# 9volt_rail.net
KiCad netlist of a schematic drawn in EAGLE
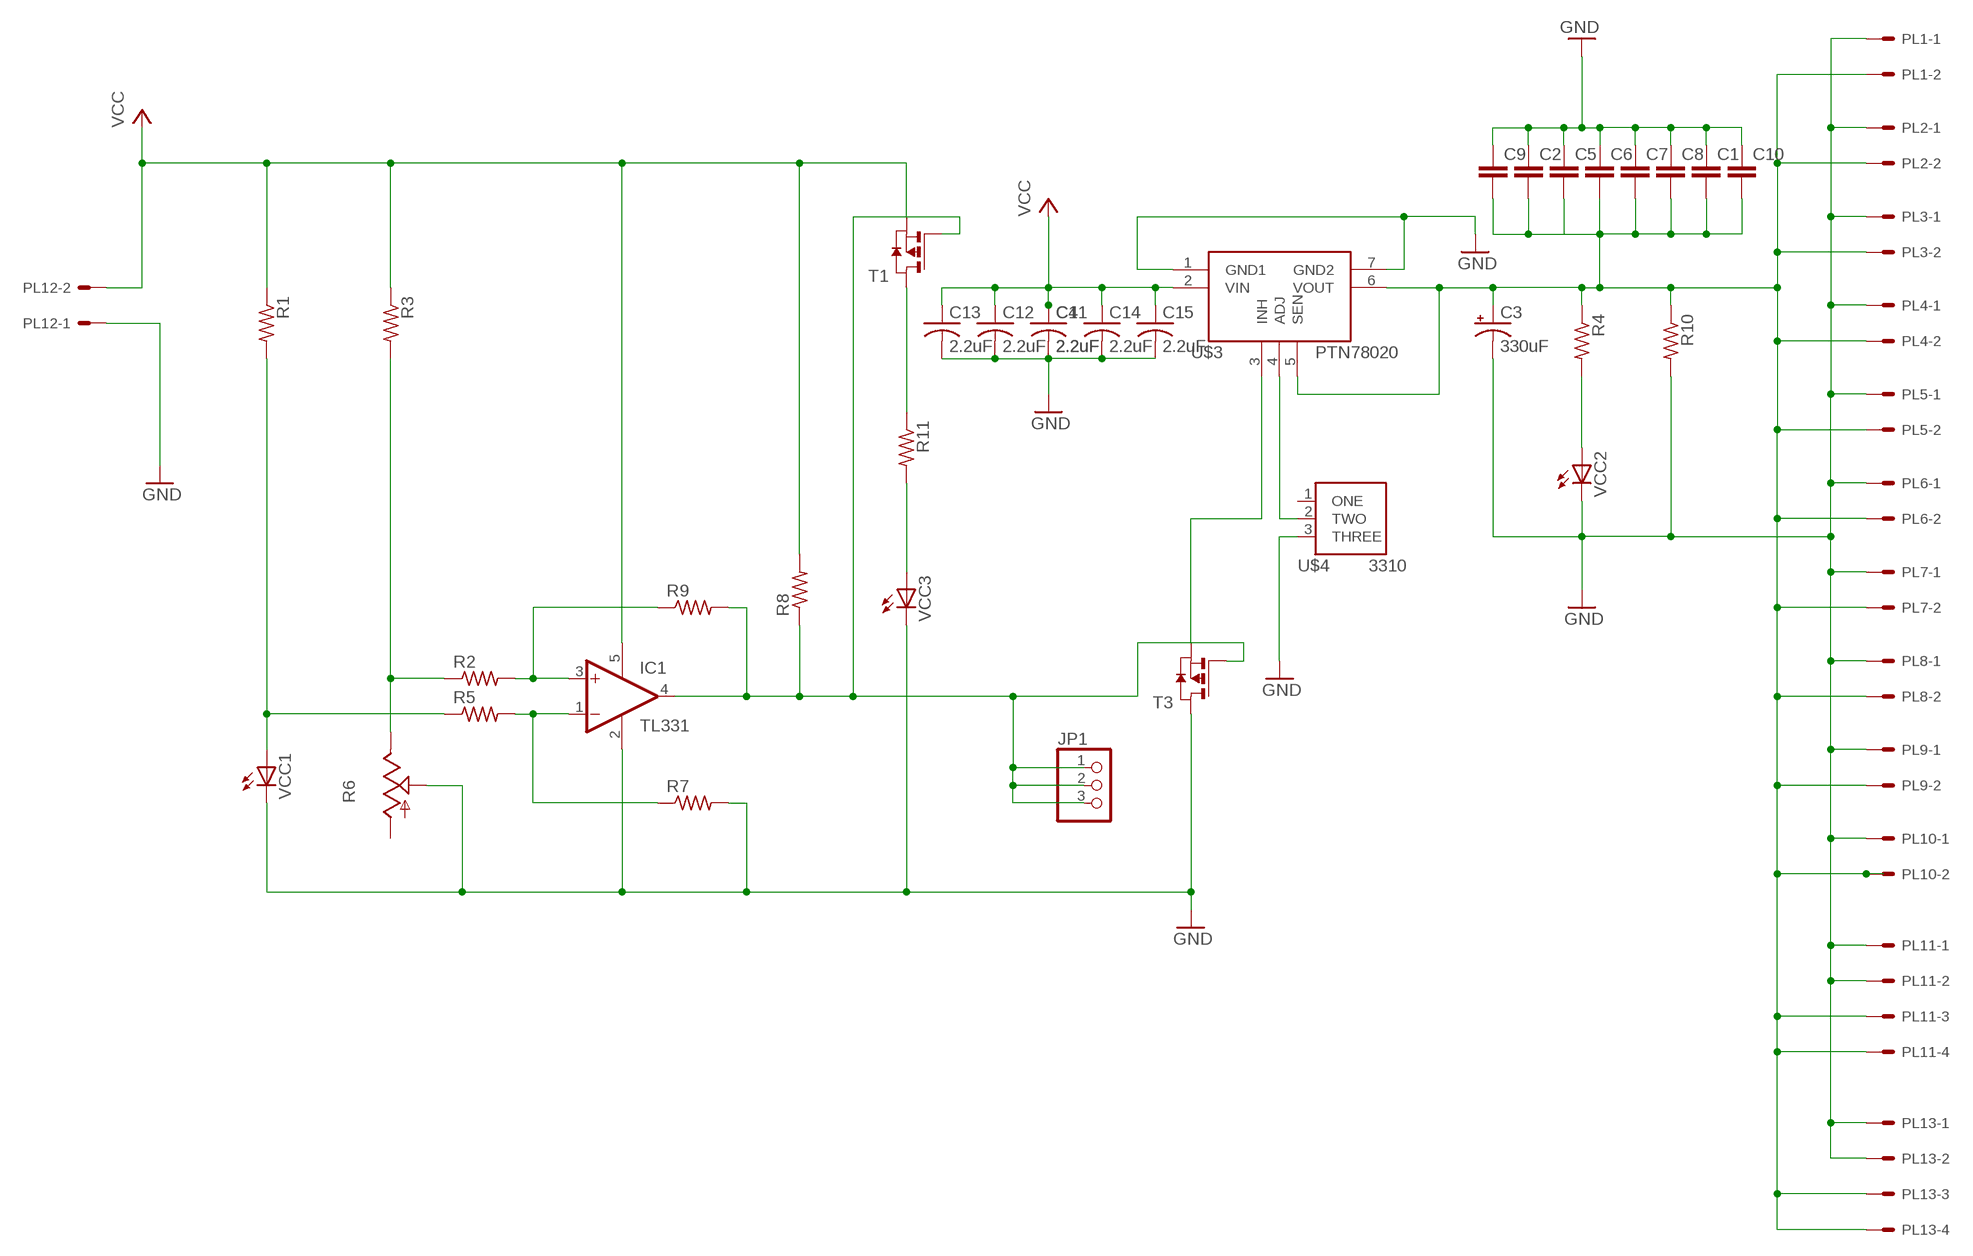
[diagram p0: schematic, sheet 1]

(export (version "E")
  (design (tool "Eeschema 10.0.6"))
  (components
    (comp (ref "C1")
      (value "C-EUC0805")
      (footprint "eagle-import:C0805")
      (libsource (lib "eagle-import") (part "C-EUC0805"))
    )
    (comp (ref "C2")
      (value "C-EUC0805")
      (footprint "eagle-import:C0805")
      (libsource (lib "eagle-import") (part "C-EUC0805"))
    )
    (comp (ref "C3")
      (value "330uF")
      (footprint "eagle-import:E5-10,5")
      (libsource (lib "eagle-import") (part "CPOL-USE5-10.5"))
    )
    (comp (ref "C4")
      (value "2.2uF")
      (footprint "eagle-import:C0805")
      (libsource (lib "eagle-import") (part "C-USC0805"))
    )
    (comp (ref "C5")
      (value "C-EUC0805")
      (footprint "eagle-import:C0805")
      (libsource (lib "eagle-import") (part "C-EUC0805"))
    )
    (comp (ref "C6")
      (value "C-EUC0805")
      (footprint "eagle-import:C0805")
      (libsource (lib "eagle-import") (part "C-EUC0805"))
    )
    (comp (ref "C7")
      (value "C-EUC0805")
      (footprint "eagle-import:C0805")
      (libsource (lib "eagle-import") (part "C-EUC0805"))
    )
    (comp (ref "C8")
      (value "C-EUC0805")
      (footprint "eagle-import:C0805")
      (libsource (lib "eagle-import") (part "C-EUC0805"))
    )
    (comp (ref "C9")
      (value "C-EUC0805")
      (footprint "eagle-import:C0805")
      (libsource (lib "eagle-import") (part "C-EUC0805"))
    )
    (comp (ref "C10")
      (value "C-EUC0805")
      (footprint "eagle-import:C0805")
      (libsource (lib "eagle-import") (part "C-EUC0805"))
    )
    (comp (ref "C11")
      (value "2.2uF")
      (footprint "eagle-import:C0805")
      (libsource (lib "eagle-import") (part "C-USC0805"))
    )
    (comp (ref "C12")
      (value "2.2uF")
      (footprint "eagle-import:C0805")
      (libsource (lib "eagle-import") (part "C-USC0805"))
    )
    (comp (ref "C13")
      (value "2.2uF")
      (footprint "eagle-import:C0805")
      (libsource (lib "eagle-import") (part "C-USC0805"))
    )
    (comp (ref "C14")
      (value "2.2uF")
      (footprint "eagle-import:C0805")
      (libsource (lib "eagle-import") (part "C-USC0805"))
    )
    (comp (ref "C15")
      (value "2.2uF")
      (footprint "eagle-import:C0805")
      (libsource (lib "eagle-import") (part "C-USC0805"))
    )
    (comp (ref "IC1")
      (value "TL331")
      (footprint "eagle-import:DBV-R-PDSO-G5")
      (libsource (lib "eagle-import") (part "TL331"))
    )
    (comp (ref "JP1")
      (value "PINHD-1X3")
      (footprint "eagle-import:1X03")
      (libsource (lib "eagle-import") (part "PINHD-1X3"))
    )
    (comp (ref "PL1")
      (value "555X-2H")
      (footprint "eagle-import:5569-2")
      (libsource (lib "eagle-import") (part "555X-2H"))
    )
    (comp (ref "PL2")
      (value "555X-2H")
      (footprint "eagle-import:5569-2")
      (libsource (lib "eagle-import") (part "555X-2H"))
    )
    (comp (ref "PL3")
      (value "555X-2H")
      (footprint "eagle-import:5569-2")
      (libsource (lib "eagle-import") (part "555X-2H"))
    )
    (comp (ref "PL4")
      (value "555X-2H")
      (footprint "eagle-import:5569-2")
      (libsource (lib "eagle-import") (part "555X-2H"))
    )
    (comp (ref "PL5")
      (value "555X-2H")
      (footprint "eagle-import:5569-2")
      (libsource (lib "eagle-import") (part "555X-2H"))
    )
    (comp (ref "PL6")
      (value "555X-2H")
      (footprint "eagle-import:5569-2")
      (libsource (lib "eagle-import") (part "555X-2H"))
    )
    (comp (ref "PL7")
      (value "555X-2H")
      (footprint "eagle-import:5569-2")
      (libsource (lib "eagle-import") (part "555X-2H"))
    )
    (comp (ref "PL8")
      (value "555X-2H")
      (footprint "eagle-import:5569-2")
      (libsource (lib "eagle-import") (part "555X-2H"))
    )
    (comp (ref "PL9")
      (value "555X-2H")
      (footprint "eagle-import:5569-2")
      (libsource (lib "eagle-import") (part "555X-2H"))
    )
    (comp (ref "PL10")
      (value "555X-2H")
      (footprint "eagle-import:5569-2")
      (libsource (lib "eagle-import") (part "555X-2H"))
    )
    (comp (ref "PL11")
      (value "555X-4H")
      (footprint "eagle-import:5569-4")
      (libsource (lib "eagle-import") (part "555X-4H"))
    )
    (comp (ref "PL12")
      (value "555X-2H")
      (footprint "eagle-import:5569-2")
      (libsource (lib "eagle-import") (part "555X-2H"))
    )
    (comp (ref "PL13")
      (value "555X-4H")
      (footprint "eagle-import:5569-4")
      (libsource (lib "eagle-import") (part "555X-4H"))
    )
    (comp (ref "R1")
      (value "R-US_M0805")
      (footprint "eagle-import:M0805")
      (libsource (lib "eagle-import") (part "R-US_M0805"))
    )
    (comp (ref "R2")
      (value "R-US_M0805")
      (footprint "eagle-import:M0805")
      (libsource (lib "eagle-import") (part "R-US_M0805"))
    )
    (comp (ref "R3")
      (value "R-US_M0805")
      (footprint "eagle-import:M0805")
      (libsource (lib "eagle-import") (part "R-US_M0805"))
    )
    (comp (ref "R4")
      (value "R-US_M0805")
      (footprint "eagle-import:M0805")
      (libsource (lib "eagle-import") (part "R-US_M0805"))
    )
    (comp (ref "R5")
      (value "R-US_M0805")
      (footprint "eagle-import:M0805")
      (libsource (lib "eagle-import") (part "R-US_M0805"))
    )
    (comp (ref "R6")
      (value "TRIM_US-RS3")
      (footprint "eagle-import:RS3")
      (libsource (lib "eagle-import") (part "TRIM_US-RS3"))
    )
    (comp (ref "R7")
      (value "R-US_M0805")
      (footprint "eagle-import:M0805")
      (libsource (lib "eagle-import") (part "R-US_M0805"))
    )
    (comp (ref "R8")
      (value "R-US_M0805")
      (footprint "eagle-import:M0805")
      (libsource (lib "eagle-import") (part "R-US_M0805"))
    )
    (comp (ref "R9")
      (value "R-US_M0805")
      (footprint "eagle-import:M0805")
      (libsource (lib "eagle-import") (part "R-US_M0805"))
    )
    (comp (ref "R10")
      (value "R-US_M0805")
      (footprint "eagle-import:M0805")
      (libsource (lib "eagle-import") (part "R-US_M0805"))
    )
    (comp (ref "R11")
      (value "R-US_M0805")
      (footprint "eagle-import:M0805")
      (libsource (lib "eagle-import") (part "R-US_M0805"))
    )
    (comp (ref "T1")
      (value "PMOSSOT223")
      (footprint "eagle-import:SOT223")
      (libsource (lib "eagle-import") (part "PMOSSOT223"))
    )
    (comp (ref "T3")
      (value "PMOSSOT223")
      (footprint "eagle-import:SOT223")
      (libsource (lib "eagle-import") (part "PMOSSOT223"))
    )
    (comp (ref "U$3")
      (value "PTH78020-SMD")
      (footprint "eagle-import:PTN78020-SND")
      (libsource (lib "eagle-import") (part "PTH78020-SMD"))
    )
    (comp (ref "U$4")
      (value "3310-001")
      (footprint "eagle-import:3310-001-TH")
      (libsource (lib "eagle-import") (part "3310-001"))
    )
    (comp (ref "VCC1")
      (value "LED5MM")
      (footprint "eagle-import:LED5MM")
      (libsource (lib "eagle-import") (part "LED5MM"))
    )
    (comp (ref "VCC2")
      (value "LED5MM")
      (footprint "eagle-import:LED5MM")
      (libsource (lib "eagle-import") (part "LED5MM"))
    )
    (comp (ref "VCC3")
      (value "LED5MM")
      (footprint "eagle-import:LED5MM")
      (libsource (lib "eagle-import") (part "LED5MM"))
    )
  )
  (nets
    (net (code "1") (name "GND") (class "Default")
      (node (ref "C1") (pin "1") (pinfunction "1_1") (pintype "passive"))
      (node (ref "C10") (pin "1") (pinfunction "1_1") (pintype "passive"))
      (node (ref "C11") (pin "2") (pinfunction "2_2") (pintype "passive"))
      (node (ref "C12") (pin "2") (pinfunction "2_2") (pintype "passive"))
      (node (ref "C13") (pin "2") (pinfunction "2_2") (pintype "passive"))
      (node (ref "C14") (pin "2") (pinfunction "2_2") (pintype "passive"))
      (node (ref "C15") (pin "2") (pinfunction "2_2") (pintype "passive"))
      (node (ref "C2") (pin "1") (pinfunction "1_1") (pintype "passive"))
      (node (ref "C3") (pin "-") (pinfunction "-_-") (pintype "passive"))
      (node (ref "C4") (pin "2") (pinfunction "2_2") (pintype "passive"))
      (node (ref "C5") (pin "1") (pinfunction "1_1") (pintype "passive"))
      (node (ref "C6") (pin "1") (pinfunction "1_1") (pintype "passive"))
      (node (ref "C7") (pin "1") (pinfunction "1_1") (pintype "passive"))
      (node (ref "C8") (pin "1") (pinfunction "1_1") (pintype "passive"))
      (node (ref "C9") (pin "1") (pinfunction "1_1") (pintype "passive"))
      (node (ref "IC1") (pin "2") (pinfunction "GND_2") (pintype "power_in"))
      (node (ref "PL1") (pin "1") (pinfunction "S_1") (pintype "passive"))
      (node (ref "PL10") (pin "1") (pinfunction "S_1") (pintype "passive"))
      (node (ref "PL11") (pin "1") (pinfunction "S_1") (pintype "passive"))
      (node (ref "PL11") (pin "2") (pinfunction "S_2") (pintype "passive"))
      (node (ref "PL12") (pin "1") (pinfunction "S_1") (pintype "passive"))
      (node (ref "PL13") (pin "1") (pinfunction "S_1") (pintype "passive"))
      (node (ref "PL13") (pin "2") (pinfunction "S_2") (pintype "passive"))
      (node (ref "PL2") (pin "1") (pinfunction "S_1") (pintype "passive"))
      (node (ref "PL3") (pin "1") (pinfunction "S_1") (pintype "passive"))
      (node (ref "PL4") (pin "1") (pinfunction "S_1") (pintype "passive"))
      (node (ref "PL5") (pin "1") (pinfunction "S_1") (pintype "passive"))
      (node (ref "PL6") (pin "1") (pinfunction "S_1") (pintype "passive"))
      (node (ref "PL7") (pin "1") (pinfunction "S_1") (pintype "passive"))
      (node (ref "PL8") (pin "1") (pinfunction "S_1") (pintype "passive"))
      (node (ref "PL9") (pin "1") (pinfunction "S_1") (pintype "passive"))
      (node (ref "R10") (pin "2") (pinfunction "2_2") (pintype "passive"))
      (node (ref "R6") (pin "S") (pinfunction "S_S") (pintype "passive"))
      (node (ref "R7") (pin "2") (pinfunction "2_2") (pintype "passive"))
      (node (ref "T3") (pin "2") (pinfunction "D_2") (pintype "passive"))
      (node (ref "T3") (pin "4") (pinfunction "D_4") (pintype "passive"))
      (node (ref "U$3") (pin "1") (pinfunction "GND1_1") (pintype "bidirectional"))
      (node (ref "U$3") (pin "7") (pinfunction "GND2_7") (pintype "bidirectional"))
      (node (ref "U$4") (pin "3") (pinfunction "THREE_3") (pintype "bidirectional"))
      (node (ref "VCC1") (pin "K") (pinfunction "C_K") (pintype "passive"))
      (node (ref "VCC2") (pin "K") (pinfunction "C_K") (pintype "passive"))
      (node (ref "VCC3") (pin "K") (pinfunction "C_K") (pintype "passive"))
    )
    (net (code "2") (name "Net-(IC1-+IN)") (class "Default")
      (node (ref "IC1") (pin "3") (pinfunction "+IN_3") (pintype "input"))
      (node (ref "R2") (pin "2") (pinfunction "2_2") (pintype "passive"))
      (node (ref "R9") (pin "1") (pinfunction "1_1") (pintype "passive"))
    )
    (net (code "3") (name "Net-(IC1--IN)") (class "Default")
      (node (ref "IC1") (pin "1") (pinfunction "-IN_1") (pintype "input"))
      (node (ref "R5") (pin "2") (pinfunction "2_2") (pintype "passive"))
      (node (ref "R7") (pin "1") (pinfunction "1_1") (pintype "passive"))
    )
    (net (code "4") (name "Net-(IC1-OUT)") (class "Default")
      (node (ref "IC1") (pin "4") (pinfunction "OUT_4") (pintype "output"))
      (node (ref "JP1") (pin "1") (pinfunction "1_1") (pintype "passive"))
      (node (ref "JP1") (pin "2") (pinfunction "2_2") (pintype "passive"))
      (node (ref "JP1") (pin "3") (pinfunction "3_3") (pintype "passive"))
      (node (ref "R8") (pin "1") (pinfunction "1_1") (pintype "passive"))
      (node (ref "R9") (pin "2") (pinfunction "2_2") (pintype "passive"))
      (node (ref "T1") (pin "1") (pinfunction "G_1") (pintype "passive"))
      (node (ref "T3") (pin "1") (pinfunction "G_1") (pintype "passive"))
    )
    (net (code "5") (name "Net-(PL10B-S)") (class "Default")
      (node (ref "C1") (pin "2") (pinfunction "2_2") (pintype "passive"))
      (node (ref "C10") (pin "2") (pinfunction "2_2") (pintype "passive"))
      (node (ref "C2") (pin "2") (pinfunction "2_2") (pintype "passive"))
      (node (ref "C3") (pin "+") (pinfunction "+_+") (pintype "passive"))
      (node (ref "C5") (pin "2") (pinfunction "2_2") (pintype "passive"))
      (node (ref "C6") (pin "2") (pinfunction "2_2") (pintype "passive"))
      (node (ref "C7") (pin "2") (pinfunction "2_2") (pintype "passive"))
      (node (ref "C8") (pin "2") (pinfunction "2_2") (pintype "passive"))
      (node (ref "C9") (pin "2") (pinfunction "2_2") (pintype "passive"))
      (node (ref "PL1") (pin "2") (pinfunction "S_2") (pintype "passive"))
      (node (ref "PL10") (pin "2") (pinfunction "S_2") (pintype "passive"))
      (node (ref "PL11") (pin "3") (pinfunction "S_3") (pintype "passive"))
      (node (ref "PL11") (pin "4") (pinfunction "S_4") (pintype "passive"))
      (node (ref "PL13") (pin "3") (pinfunction "S_3") (pintype "passive"))
      (node (ref "PL13") (pin "4") (pinfunction "S_4") (pintype "passive"))
      (node (ref "PL2") (pin "2") (pinfunction "S_2") (pintype "passive"))
      (node (ref "PL3") (pin "2") (pinfunction "S_2") (pintype "passive"))
      (node (ref "PL4") (pin "2") (pinfunction "S_2") (pintype "passive"))
      (node (ref "PL5") (pin "2") (pinfunction "S_2") (pintype "passive"))
      (node (ref "PL6") (pin "2") (pinfunction "S_2") (pintype "passive"))
      (node (ref "PL7") (pin "2") (pinfunction "S_2") (pintype "passive"))
      (node (ref "PL8") (pin "2") (pinfunction "S_2") (pintype "passive"))
      (node (ref "PL9") (pin "2") (pinfunction "S_2") (pintype "passive"))
      (node (ref "R10") (pin "1") (pinfunction "1_1") (pintype "passive"))
      (node (ref "R4") (pin "1") (pinfunction "1_1") (pintype "passive"))
      (node (ref "U$3") (pin "5") (pinfunction "SEN_5") (pintype "bidirectional"))
      (node (ref "U$3") (pin "6") (pinfunction "VOUT_6") (pintype "bidirectional"))
    )
    (net (code "6") (name "Net-(R1-Pad2)") (class "Default")
      (node (ref "R1") (pin "2") (pinfunction "2_2") (pintype "passive"))
      (node (ref "R5") (pin "1") (pinfunction "1_1") (pintype "passive"))
      (node (ref "VCC1") (pin "A") (pinfunction "A_A") (pintype "passive"))
    )
    (net (code "7") (name "Net-(R2-Pad1)") (class "Default")
      (node (ref "R2") (pin "1") (pinfunction "1_1") (pintype "passive"))
      (node (ref "R3") (pin "2") (pinfunction "2_2") (pintype "passive"))
      (node (ref "R6") (pin "E") (pinfunction "E_E") (pintype "passive"))
    )
    (net (code "8") (name "Net-(R4-Pad2)") (class "Default")
      (node (ref "R4") (pin "2") (pinfunction "2_2") (pintype "passive"))
      (node (ref "VCC2") (pin "A") (pinfunction "A_A") (pintype "passive"))
    )
    (net (code "9") (name "Net-(R11-Pad1)") (class "Default")
      (node (ref "R11") (pin "1") (pinfunction "1_1") (pintype "passive"))
      (node (ref "T1") (pin "2") (pinfunction "D_2") (pintype "passive"))
      (node (ref "T1") (pin "4") (pinfunction "D_4") (pintype "passive"))
    )
    (net (code "10") (name "Net-(R11-Pad2)") (class "Default")
      (node (ref "R11") (pin "2") (pinfunction "2_2") (pintype "passive"))
      (node (ref "VCC3") (pin "A") (pinfunction "A_A") (pintype "passive"))
    )
    (net (code "11") (name "Net-(T3-S)") (class "Default")
      (node (ref "T3") (pin "3") (pinfunction "S_3") (pintype "passive"))
      (node (ref "U$3") (pin "3") (pinfunction "INH_3") (pintype "bidirectional"))
    )
    (net (code "12") (name "Net-(U$3-ADJ)") (class "Default")
      (node (ref "U$3") (pin "4") (pinfunction "ADJ_4") (pintype "bidirectional"))
      (node (ref "U$4") (pin "2") (pinfunction "TWO_2") (pintype "bidirectional"))
    )
    (net (code "13") (name "VCC") (class "Default")
      (node (ref "C11") (pin "1") (pinfunction "1_1") (pintype "passive"))
      (node (ref "C12") (pin "1") (pinfunction "1_1") (pintype "passive"))
      (node (ref "C13") (pin "1") (pinfunction "1_1") (pintype "passive"))
      (node (ref "C14") (pin "1") (pinfunction "1_1") (pintype "passive"))
      (node (ref "C15") (pin "1") (pinfunction "1_1") (pintype "passive"))
      (node (ref "C4") (pin "1") (pinfunction "1_1") (pintype "passive"))
      (node (ref "IC1") (pin "5") (pinfunction "V+_5") (pintype "power_in"))
      (node (ref "PL12") (pin "2") (pinfunction "S_2") (pintype "passive"))
      (node (ref "R1") (pin "1") (pinfunction "1_1") (pintype "passive"))
      (node (ref "R3") (pin "1") (pinfunction "1_1") (pintype "passive"))
      (node (ref "R8") (pin "2") (pinfunction "2_2") (pintype "passive"))
      (node (ref "T1") (pin "3") (pinfunction "S_3") (pintype "passive"))
      (node (ref "U$3") (pin "2") (pinfunction "VIN_2") (pintype "bidirectional"))
    )
    (net (code "14") (name "unconnected-(R6-PadA)") (class "Default")
      (node (ref "R6") (pin "A") (pinfunction "A_A") (pintype "passive"))
    )
    (net (code "15") (name "unconnected-(U$4-ONE-Pad1)") (class "Default")
      (node (ref "U$4") (pin "1") (pinfunction "ONE_1") (pintype "bidirectional"))
    )
  )
)
